# Versie_3.net
KiCad netlist of a schematic drawn in EAGLE
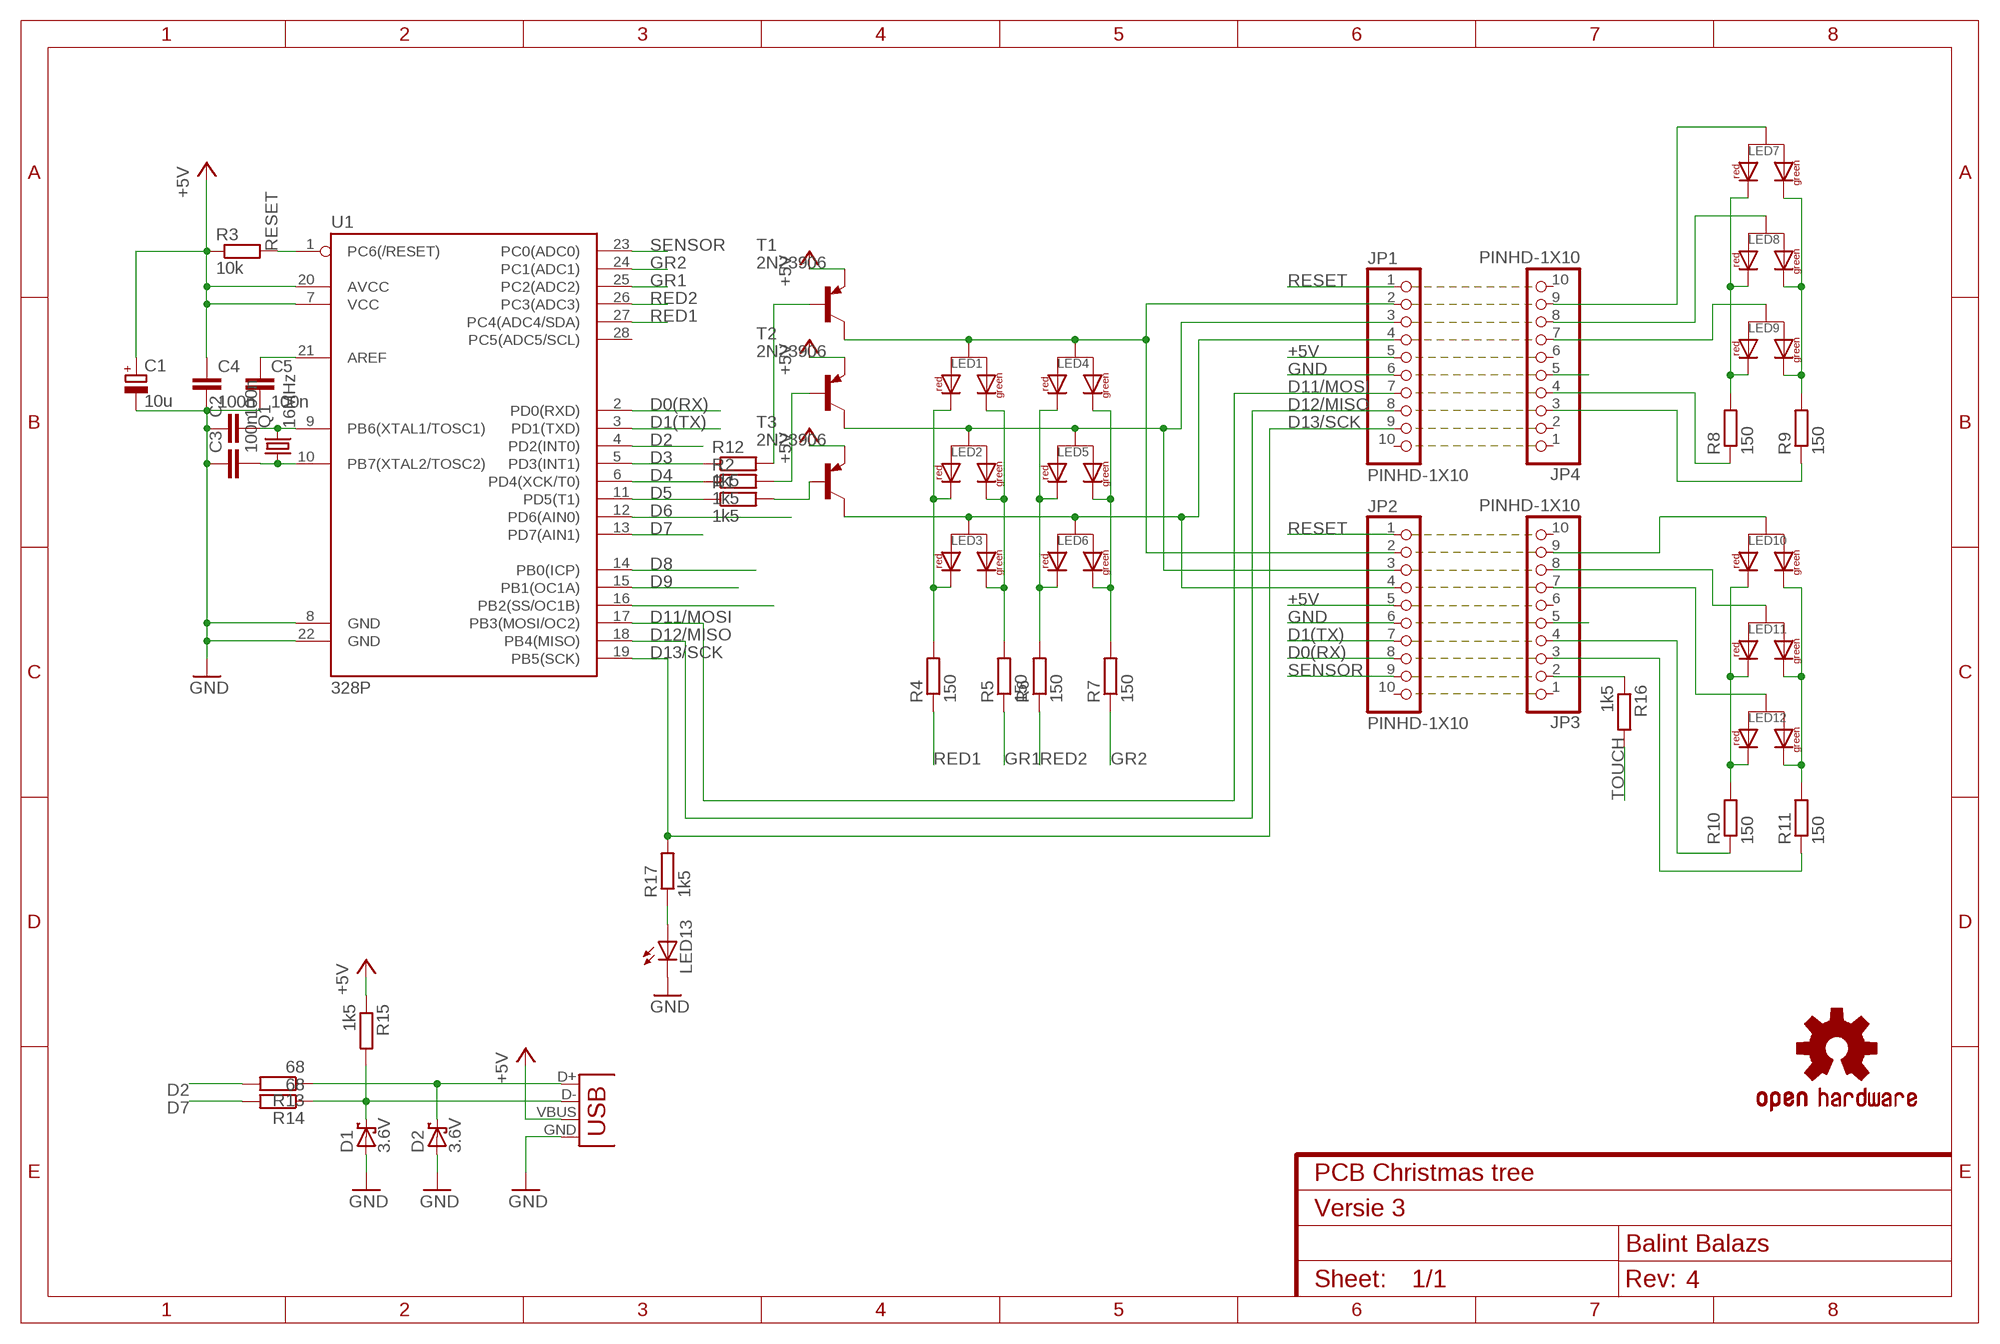
[diagram p0: schematic, sheet 1]

(export (version "E")
  (design (tool "Eeschema 10.0.6"))
  (components
    (comp (ref "C1")
      (value "10u")
      (footprint "eagle-import:E2-4")
      (libsource (lib "eagle-import") (part "CPOL-EUE2-4"))
    )
    (comp (ref "C2")
      (value "100n")
      (footprint "eagle-import:C025-024X044")
      (libsource (lib "eagle-import") (part "C-EU025-024X044"))
    )
    (comp (ref "C3")
      (value "100n")
      (footprint "eagle-import:C025-024X044")
      (libsource (lib "eagle-import") (part "C-EU025-024X044"))
    )
    (comp (ref "C4")
      (value "100n")
      (footprint "eagle-import:C025-024X044")
      (libsource (lib "eagle-import") (part "C-EU025-024X044"))
    )
    (comp (ref "C5")
      (value "100n")
      (footprint "eagle-import:C025-024X044")
      (libsource (lib "eagle-import") (part "C-EU025-024X044"))
    )
    (comp (ref "D1")
      (value "3.6V")
      (footprint "eagle-import:DO41-7.6")
      (libsource (lib "eagle-import") (part "1N5817-B"))
    )
    (comp (ref "D2")
      (value "3.6V")
      (footprint "eagle-import:DO41-7.6")
      (libsource (lib "eagle-import") (part "1N5817-B"))
    )
    (comp (ref "JP1")
      (value "PINHD-1X10")
      (footprint "eagle-import:1X10-BIG")
      (libsource (lib "eagle-import") (part "PINHD-1X10"))
    )
    (comp (ref "JP2")
      (value "PINHD-1X10")
      (footprint "eagle-import:1X10-BIG")
      (libsource (lib "eagle-import") (part "PINHD-1X10"))
    )
    (comp (ref "JP3")
      (value "PINHD-1X10")
      (footprint "eagle-import:1X10-BIG")
      (libsource (lib "eagle-import") (part "PINHD-1X10"))
    )
    (comp (ref "JP4")
      (value "PINHD-1X10")
      (footprint "eagle-import:1X10-BIG")
      (libsource (lib "eagle-import") (part "PINHD-1X10"))
    )
    (comp (ref "LED1")
      (value "KPBA-3010SURKCGKC3MM")
      (footprint "eagle-import:3MMLED")
      (libsource (lib "eagle-import") (part "KPBA-3010SURKCGKC3MM"))
    )
    (comp (ref "LED2")
      (value "KPBA-3010SURKCGKC3MM")
      (footprint "eagle-import:3MMLED")
      (libsource (lib "eagle-import") (part "KPBA-3010SURKCGKC3MM"))
    )
    (comp (ref "LED3")
      (value "KPBA-3010SURKCGKC3MM")
      (footprint "eagle-import:3MMLED")
      (libsource (lib "eagle-import") (part "KPBA-3010SURKCGKC3MM"))
    )
    (comp (ref "LED4")
      (value "KPBA-3010SURKCGKC3MM")
      (footprint "eagle-import:3MMLED")
      (libsource (lib "eagle-import") (part "KPBA-3010SURKCGKC3MM"))
    )
    (comp (ref "LED5")
      (value "KPBA-3010SURKCGKC3MM")
      (footprint "eagle-import:3MMLED")
      (libsource (lib "eagle-import") (part "KPBA-3010SURKCGKC3MM"))
    )
    (comp (ref "LED6")
      (value "KPBA-3010SURKCGKC3MM")
      (footprint "eagle-import:3MMLED")
      (libsource (lib "eagle-import") (part "KPBA-3010SURKCGKC3MM"))
    )
    (comp (ref "LED7")
      (value "KPBA-3010SURKCGKC3MM")
      (footprint "eagle-import:3MMLED")
      (libsource (lib "eagle-import") (part "KPBA-3010SURKCGKC3MM"))
    )
    (comp (ref "LED8")
      (value "KPBA-3010SURKCGKC3MM")
      (footprint "eagle-import:3MMLED")
      (libsource (lib "eagle-import") (part "KPBA-3010SURKCGKC3MM"))
    )
    (comp (ref "LED9")
      (value "KPBA-3010SURKCGKC3MM")
      (footprint "eagle-import:3MMLED")
      (libsource (lib "eagle-import") (part "KPBA-3010SURKCGKC3MM"))
    )
    (comp (ref "LED10")
      (value "KPBA-3010SURKCGKC3MM")
      (footprint "eagle-import:3MMLED")
      (libsource (lib "eagle-import") (part "KPBA-3010SURKCGKC3MM"))
    )
    (comp (ref "LED11")
      (value "KPBA-3010SURKCGKC3MM")
      (footprint "eagle-import:3MMLED")
      (libsource (lib "eagle-import") (part "KPBA-3010SURKCGKC3MM"))
    )
    (comp (ref "LED12")
      (value "KPBA-3010SURKCGKC3MM")
      (footprint "eagle-import:3MMLED")
      (libsource (lib "eagle-import") (part "KPBA-3010SURKCGKC3MM"))
    )
    (comp (ref "LED13")
      (value "LED5MM")
      (footprint "eagle-import:LED5MM")
      (libsource (lib "eagle-import") (part "LED5MM"))
    )
    (comp (ref "LOGO1")
      (value "OSHW-LOGOM")
      (footprint "eagle-import:OSHW-LOGO-M")
      (libsource (lib "eagle-import") (part "OSHW-LOGOM"))
    )
    (comp (ref "Q1")
      (value "16MHz")
      (footprint "eagle-import:HC49_S")
      (libsource (lib "eagle-import") (part "CRYSTALHC49S"))
    )
    (comp (ref "R1")
      (value "1k5")
      (footprint "eagle-import:0204_7")
      (libsource (lib "eagle-import") (part "R-EU_0204/7"))
    )
    (comp (ref "R2")
      (value "1k5")
      (footprint "eagle-import:0204_7")
      (libsource (lib "eagle-import") (part "R-EU_0204/7"))
    )
    (comp (ref "R3")
      (value "10k")
      (footprint "eagle-import:0204_7")
      (libsource (lib "eagle-import") (part "resistor_R-EU_0204/7"))
    )
    (comp (ref "R4")
      (value "150")
      (footprint "eagle-import:0204_7")
      (libsource (lib "eagle-import") (part "resistor_R-EU_0204/7"))
    )
    (comp (ref "R5")
      (value "150")
      (footprint "eagle-import:0204_7")
      (libsource (lib "eagle-import") (part "resistor_R-EU_0204/7"))
    )
    (comp (ref "R6")
      (value "150")
      (footprint "eagle-import:0204_7")
      (libsource (lib "eagle-import") (part "resistor_R-EU_0204/7"))
    )
    (comp (ref "R7")
      (value "150")
      (footprint "eagle-import:0204_7")
      (libsource (lib "eagle-import") (part "resistor_R-EU_0204/7"))
    )
    (comp (ref "R8")
      (value "150")
      (footprint "eagle-import:0204_7")
      (libsource (lib "eagle-import") (part "resistor_R-EU_0204/7"))
    )
    (comp (ref "R9")
      (value "150")
      (footprint "eagle-import:0204_7")
      (libsource (lib "eagle-import") (part "resistor_R-EU_0204/7"))
    )
    (comp (ref "R10")
      (value "150")
      (footprint "eagle-import:0204_7")
      (libsource (lib "eagle-import") (part "resistor_R-EU_0204/7"))
    )
    (comp (ref "R11")
      (value "150")
      (footprint "eagle-import:0204_7")
      (libsource (lib "eagle-import") (part "resistor_R-EU_0204/7"))
    )
    (comp (ref "R12")
      (value "1k5")
      (footprint "eagle-import:0204_7")
      (libsource (lib "eagle-import") (part "R-EU_0204/7"))
    )
    (comp (ref "R13")
      (value "68")
      (footprint "eagle-import:0204_7")
      (libsource (lib "eagle-import") (part "resistor_R-EU_0204/7"))
    )
    (comp (ref "R14")
      (value "68")
      (footprint "eagle-import:0204_7")
      (libsource (lib "eagle-import") (part "resistor_R-EU_0204/7"))
    )
    (comp (ref "R15")
      (value "1k5")
      (footprint "eagle-import:0204_7")
      (libsource (lib "eagle-import") (part "resistor_R-EU_0204/7"))
    )
    (comp (ref "R16")
      (value "1k5")
      (footprint "eagle-import:0204_7")
      (libsource (lib "eagle-import") (part "resistor_R-EU_0204/7"))
    )
    (comp (ref "R17")
      (value "1k5")
      (footprint "eagle-import:0204_7")
      (libsource (lib "eagle-import") (part "resistor_R-EU_0204/7"))
    )
    (comp (ref "T1")
      (value "2N23906")
      (footprint "eagle-import:TO92-STRAIGHT")
      (libsource (lib "eagle-import") (part "PNP"))
    )
    (comp (ref "T2")
      (value "2N23906")
      (footprint "eagle-import:TO92-STRAIGHT")
      (libsource (lib "eagle-import") (part "PNP"))
    )
    (comp (ref "T3")
      (value "2N23906")
      (footprint "eagle-import:TO92-STRAIGHT")
      (libsource (lib "eagle-import") (part "PNP"))
    )
    (comp (ref "U1")
      (value "328P")
      (footprint "eagle-import:DIP28")
      (libsource (lib "eagle-import") (part "ATMEGA328P_PDIP"))
    )
    (comp (ref "X1")
      (value "USBMINITHT")
      (footprint "eagle-import:USB-MINIB-THT")
      (libsource (lib "eagle-import") (part "USBMINITHT"))
    )
  )
  (nets
    (net (code "1") (name "+5V") (class "Default")
      (node (ref "C1") (pin "+") (pinfunction "+_+") (pintype "passive"))
      (node (ref "C4") (pin "1") (pinfunction "1_1") (pintype "passive"))
      (node (ref "JP1") (pin "5") (pinfunction "5_5") (pintype "passive"))
      (node (ref "JP2") (pin "5") (pinfunction "5_5") (pintype "passive"))
      (node (ref "R15") (pin "1") (pinfunction "1_1") (pintype "passive"))
      (node (ref "R3") (pin "1") (pinfunction "1_1") (pintype "passive"))
      (node (ref "T1") (pin "E") (pinfunction "E_E") (pintype "passive"))
      (node (ref "T2") (pin "E") (pinfunction "E_E") (pintype "passive"))
      (node (ref "T3") (pin "E") (pinfunction "E_E") (pintype "passive"))
      (node (ref "U1") (pin "20") (pinfunction "AVCC_20") (pintype "bidirectional"))
      (node (ref "U1") (pin "7") (pinfunction "VCC_7") (pintype "bidirectional"))
      (node (ref "X1") (pin "VBUS") (pinfunction "VBUS_VBUS") (pintype "bidirectional"))
    )
    (net (code "2") (name "/D0(RX)") (class "Default")
      (node (ref "JP2") (pin "8") (pinfunction "8_8") (pintype "passive"))
      (node (ref "U1") (pin "2") (pinfunction "PD0(RXD)_2") (pintype "bidirectional"))
    )
    (net (code "3") (name "/D1(TX)") (class "Default")
      (node (ref "JP2") (pin "7") (pinfunction "7_7") (pintype "passive"))
      (node (ref "U1") (pin "3") (pinfunction "PD1(TXD)_3") (pintype "bidirectional"))
    )
    (net (code "4") (name "/D2") (class "Default")
      (node (ref "R13") (pin "2") (pinfunction "2_2") (pintype "passive"))
      (node (ref "U1") (pin "4") (pinfunction "PD2(INT0)_4") (pintype "bidirectional"))
    )
    (net (code "5") (name "/D3") (class "Default")
      (node (ref "R12") (pin "1") (pinfunction "1_1") (pintype "passive"))
      (node (ref "U1") (pin "5") (pinfunction "PD3(INT1)_5") (pintype "bidirectional"))
    )
    (net (code "6") (name "/D4") (class "Default")
      (node (ref "R2") (pin "1") (pinfunction "1_1") (pintype "passive"))
      (node (ref "U1") (pin "6") (pinfunction "PD4(XCK/T0)_6") (pintype "bidirectional"))
    )
    (net (code "7") (name "/D5") (class "Default")
      (node (ref "R1") (pin "1") (pinfunction "1_1") (pintype "passive"))
      (node (ref "U1") (pin "11") (pinfunction "PD5(T1)_11") (pintype "bidirectional"))
    )
    (net (code "8") (name "/D6") (class "Default")
      (node (ref "U1") (pin "12") (pinfunction "PD6(AIN0)_12") (pintype "bidirectional"))
    )
    (net (code "9") (name "/D7") (class "Default")
      (node (ref "R14") (pin "2") (pinfunction "2_2") (pintype "passive"))
      (node (ref "U1") (pin "13") (pinfunction "PD7(AIN1)_13") (pintype "bidirectional"))
    )
    (net (code "10") (name "/D8") (class "Default")
      (node (ref "U1") (pin "14") (pinfunction "PB0(ICP)_14") (pintype "bidirectional"))
    )
    (net (code "11") (name "/D9") (class "Default")
      (node (ref "U1") (pin "15") (pinfunction "PB1(OC1A)_15") (pintype "bidirectional"))
    )
    (net (code "12") (name "/D11{slash}MOSI") (class "Default")
      (node (ref "JP1") (pin "7") (pinfunction "7_7") (pintype "passive"))
      (node (ref "U1") (pin "17") (pinfunction "PB3(MOSI/OC2)_17") (pintype "bidirectional"))
    )
    (net (code "13") (name "/D12{slash}MISO") (class "Default")
      (node (ref "JP1") (pin "8") (pinfunction "8_8") (pintype "passive"))
      (node (ref "U1") (pin "18") (pinfunction "PB4(MISO)_18") (pintype "bidirectional"))
    )
    (net (code "14") (name "/D13{slash}SCK") (class "Default")
      (node (ref "JP1") (pin "9") (pinfunction "9_9") (pintype "passive"))
      (node (ref "R17") (pin "2") (pinfunction "2_2") (pintype "passive"))
      (node (ref "U1") (pin "19") (pinfunction "PB5(SCK)_19") (pintype "bidirectional"))
    )
    (net (code "15") (name "/GR1") (class "Default")
      (node (ref "R5") (pin "1") (pinfunction "1_1") (pintype "passive"))
      (node (ref "U1") (pin "25") (pinfunction "PC2(ADC2)_25") (pintype "bidirectional"))
    )
    (net (code "16") (name "/GR2") (class "Default")
      (node (ref "R7") (pin "1") (pinfunction "1_1") (pintype "passive"))
      (node (ref "U1") (pin "24") (pinfunction "PC1(ADC1)_24") (pintype "bidirectional"))
    )
    (net (code "17") (name "/RED1") (class "Default")
      (node (ref "R4") (pin "1") (pinfunction "1_1") (pintype "passive"))
      (node (ref "U1") (pin "27") (pinfunction "PC4(ADC4/SDA)_27") (pintype "bidirectional"))
    )
    (net (code "18") (name "/RED2") (class "Default")
      (node (ref "R6") (pin "1") (pinfunction "1_1") (pintype "passive"))
      (node (ref "U1") (pin "26") (pinfunction "PC3(ADC3)_26") (pintype "bidirectional"))
    )
    (net (code "19") (name "/RESET") (class "Default")
      (node (ref "JP1") (pin "1") (pinfunction "1_1") (pintype "passive"))
      (node (ref "JP2") (pin "1") (pinfunction "1_1") (pintype "passive"))
      (node (ref "R3") (pin "2") (pinfunction "2_2") (pintype "passive"))
      (node (ref "U1") (pin "1") (pinfunction "PC6(/RESET)_1") (pintype "bidirectional"))
    )
    (net (code "20") (name "/SENSOR") (class "Default")
      (node (ref "JP2") (pin "9") (pinfunction "9_9") (pintype "passive"))
      (node (ref "U1") (pin "23") (pinfunction "PC0(ADC0)_23") (pintype "bidirectional"))
    )
    (net (code "21") (name "/TOUCH") (class "Default")
      (node (ref "R16") (pin "2") (pinfunction "2_2") (pintype "passive"))
    )
    (net (code "22") (name "GND") (class "Default")
      (node (ref "C1") (pin "-") (pinfunction "-_-") (pintype "passive"))
      (node (ref "C2") (pin "1") (pinfunction "1_1") (pintype "passive"))
      (node (ref "C3") (pin "1") (pinfunction "1_1") (pintype "passive"))
      (node (ref "C4") (pin "2") (pinfunction "2_2") (pintype "passive"))
      (node (ref "C5") (pin "2") (pinfunction "2_2") (pintype "passive"))
      (node (ref "D1") (pin "A") (pinfunction "A_A") (pintype "passive"))
      (node (ref "D2") (pin "A") (pinfunction "A_A") (pintype "passive"))
      (node (ref "JP1") (pin "6") (pinfunction "6_6") (pintype "passive"))
      (node (ref "JP2") (pin "6") (pinfunction "6_6") (pintype "passive"))
      (node (ref "LED13") (pin "K") (pinfunction "C_K") (pintype "passive"))
      (node (ref "U1") (pin "22") (pinfunction "GND_22") (pintype "bidirectional"))
      (node (ref "U1") (pin "8") (pinfunction "GND_8") (pintype "bidirectional"))
      (node (ref "X1") (pin "GND") (pinfunction "GND_GND") (pintype "bidirectional"))
    )
    (net (code "23") (name "Net-(D1-PadC)") (class "Default")
      (node (ref "D1") (pin "C") (pinfunction "C_C") (pintype "passive"))
      (node (ref "R14") (pin "1") (pinfunction "1_1") (pintype "passive"))
      (node (ref "R15") (pin "2") (pinfunction "2_2") (pintype "passive"))
      (node (ref "X1") (pin "D-") (pinfunction "D-_D-") (pintype "bidirectional"))
    )
    (net (code "24") (name "Net-(D2-PadC)") (class "Default")
      (node (ref "D2") (pin "C") (pinfunction "C_C") (pintype "passive"))
      (node (ref "R13") (pin "1") (pinfunction "1_1") (pintype "passive"))
      (node (ref "X1") (pin "D+") (pinfunction "D+_D+") (pintype "bidirectional"))
    )
    (net (code "25") (name "Net-(JP3-Pad2)") (class "Default")
      (node (ref "JP3") (pin "2") (pinfunction "2_2") (pintype "passive"))
      (node (ref "R16") (pin "1") (pinfunction "1_1") (pintype "passive"))
    )
    (net (code "26") (name "Net-(JP3-Pad3)") (class "Default")
      (node (ref "JP3") (pin "3") (pinfunction "3_3") (pintype "passive"))
      (node (ref "R11") (pin "1") (pinfunction "1_1") (pintype "passive"))
    )
    (net (code "27") (name "Net-(JP3-Pad4)") (class "Default")
      (node (ref "JP3") (pin "4") (pinfunction "4_4") (pintype "passive"))
      (node (ref "R10") (pin "1") (pinfunction "1_1") (pintype "passive"))
    )
    (net (code "28") (name "Net-(JP4-Pad3)") (class "Default")
      (node (ref "JP4") (pin "3") (pinfunction "3_3") (pintype "passive"))
      (node (ref "R9") (pin "1") (pinfunction "1_1") (pintype "passive"))
    )
    (net (code "29") (name "Net-(JP4-Pad4)") (class "Default")
      (node (ref "JP4") (pin "4") (pinfunction "4_4") (pintype "passive"))
      (node (ref "R8") (pin "1") (pinfunction "1_1") (pintype "passive"))
    )
    (net (code "30") (name "Net-(LED1-P$1)") (class "Default")
      (node (ref "JP1") (pin "2") (pinfunction "2_2") (pintype "passive"))
      (node (ref "JP2") (pin "2") (pinfunction "2_2") (pintype "passive"))
      (node (ref "LED1") (pin "+") (pinfunction "P$1_+") (pintype "passive"))
      (node (ref "LED4") (pin "+") (pinfunction "P$1_+") (pintype "passive"))
      (node (ref "T1") (pin "C") (pinfunction "C_C") (pintype "passive"))
    )
    (net (code "31") (name "Net-(LED1-P$2)") (class "Default")
      (node (ref "LED1") (pin "-1") (pinfunction "P$2_-1") (pintype "passive"))
      (node (ref "LED2") (pin "-1") (pinfunction "P$2_-1") (pintype "passive"))
      (node (ref "LED3") (pin "-1") (pinfunction "P$2_-1") (pintype "passive"))
      (node (ref "R4") (pin "2") (pinfunction "2_2") (pintype "passive"))
    )
    (net (code "32") (name "Net-(LED1-P$3)") (class "Default")
      (node (ref "LED1") (pin "-2") (pinfunction "P$3_-2") (pintype "passive"))
      (node (ref "LED2") (pin "-2") (pinfunction "P$3_-2") (pintype "passive"))
      (node (ref "LED3") (pin "-2") (pinfunction "P$3_-2") (pintype "passive"))
      (node (ref "R5") (pin "2") (pinfunction "2_2") (pintype "passive"))
    )
    (net (code "33") (name "Net-(LED2-P$1)") (class "Default")
      (node (ref "JP1") (pin "3") (pinfunction "3_3") (pintype "passive"))
      (node (ref "JP2") (pin "3") (pinfunction "3_3") (pintype "passive"))
      (node (ref "LED2") (pin "+") (pinfunction "P$1_+") (pintype "passive"))
      (node (ref "LED5") (pin "+") (pinfunction "P$1_+") (pintype "passive"))
      (node (ref "T2") (pin "C") (pinfunction "C_C") (pintype "passive"))
    )
    (net (code "34") (name "Net-(LED3-P$1)") (class "Default")
      (node (ref "JP1") (pin "4") (pinfunction "4_4") (pintype "passive"))
      (node (ref "JP2") (pin "4") (pinfunction "4_4") (pintype "passive"))
      (node (ref "LED3") (pin "+") (pinfunction "P$1_+") (pintype "passive"))
      (node (ref "LED6") (pin "+") (pinfunction "P$1_+") (pintype "passive"))
      (node (ref "T3") (pin "C") (pinfunction "C_C") (pintype "passive"))
    )
    (net (code "35") (name "Net-(LED4-P$2)") (class "Default")
      (node (ref "LED4") (pin "-1") (pinfunction "P$2_-1") (pintype "passive"))
      (node (ref "LED5") (pin "-1") (pinfunction "P$2_-1") (pintype "passive"))
      (node (ref "LED6") (pin "-1") (pinfunction "P$2_-1") (pintype "passive"))
      (node (ref "R6") (pin "2") (pinfunction "2_2") (pintype "passive"))
    )
    (net (code "36") (name "Net-(LED4-P$3)") (class "Default")
      (node (ref "LED4") (pin "-2") (pinfunction "P$3_-2") (pintype "passive"))
      (node (ref "LED5") (pin "-2") (pinfunction "P$3_-2") (pintype "passive"))
      (node (ref "LED6") (pin "-2") (pinfunction "P$3_-2") (pintype "passive"))
      (node (ref "R7") (pin "2") (pinfunction "2_2") (pintype "passive"))
    )
    (net (code "37") (name "Net-(LED7-P$1)") (class "Default")
      (node (ref "JP4") (pin "9") (pinfunction "9_9") (pintype "passive"))
      (node (ref "LED7") (pin "+") (pinfunction "P$1_+") (pintype "passive"))
    )
    (net (code "38") (name "Net-(LED7-P$2)") (class "Default")
      (node (ref "LED7") (pin "-1") (pinfunction "P$2_-1") (pintype "passive"))
      (node (ref "LED8") (pin "-1") (pinfunction "P$2_-1") (pintype "passive"))
      (node (ref "LED9") (pin "-1") (pinfunction "P$2_-1") (pintype "passive"))
      (node (ref "R8") (pin "2") (pinfunction "2_2") (pintype "passive"))
    )
    (net (code "39") (name "Net-(LED7-P$3)") (class "Default")
      (node (ref "LED7") (pin "-2") (pinfunction "P$3_-2") (pintype "passive"))
      (node (ref "LED8") (pin "-2") (pinfunction "P$3_-2") (pintype "passive"))
      (node (ref "LED9") (pin "-2") (pinfunction "P$3_-2") (pintype "passive"))
      (node (ref "R9") (pin "2") (pinfunction "2_2") (pintype "passive"))
    )
    (net (code "40") (name "Net-(LED8-P$1)") (class "Default")
      (node (ref "JP4") (pin "8") (pinfunction "8_8") (pintype "passive"))
      (node (ref "LED8") (pin "+") (pinfunction "P$1_+") (pintype "passive"))
    )
    (net (code "41") (name "Net-(LED9-P$1)") (class "Default")
      (node (ref "JP4") (pin "7") (pinfunction "7_7") (pintype "passive"))
      (node (ref "LED9") (pin "+") (pinfunction "P$1_+") (pintype "passive"))
    )
    (net (code "42") (name "Net-(LED10-P$1)") (class "Default")
      (node (ref "JP3") (pin "9") (pinfunction "9_9") (pintype "passive"))
      (node (ref "LED10") (pin "+") (pinfunction "P$1_+") (pintype "passive"))
    )
    (net (code "43") (name "Net-(LED10-P$2)") (class "Default")
      (node (ref "LED10") (pin "-1") (pinfunction "P$2_-1") (pintype "passive"))
      (node (ref "LED11") (pin "-1") (pinfunction "P$2_-1") (pintype "passive"))
      (node (ref "LED12") (pin "-1") (pinfunction "P$2_-1") (pintype "passive"))
      (node (ref "R10") (pin "2") (pinfunction "2_2") (pintype "passive"))
    )
    (net (code "44") (name "Net-(LED10-P$3)") (class "Default")
      (node (ref "LED10") (pin "-2") (pinfunction "P$3_-2") (pintype "passive"))
      (node (ref "LED11") (pin "-2") (pinfunction "P$3_-2") (pintype "passive"))
      (node (ref "LED12") (pin "-2") (pinfunction "P$3_-2") (pintype "passive"))
      (node (ref "R11") (pin "2") (pinfunction "2_2") (pintype "passive"))
    )
    (net (code "45") (name "Net-(LED11-P$1)") (class "Default")
      (node (ref "JP3") (pin "8") (pinfunction "8_8") (pintype "passive"))
      (node (ref "LED11") (pin "+") (pinfunction "P$1_+") (pintype "passive"))
    )
    (net (code "46") (name "Net-(LED12-P$1)") (class "Default")
      (node (ref "JP3") (pin "7") (pinfunction "7_7") (pintype "passive"))
      (node (ref "LED12") (pin "+") (pinfunction "P$1_+") (pintype "passive"))
    )
    (net (code "47") (name "Net-(LED13-PadA)") (class "Default")
      (node (ref "LED13") (pin "A") (pinfunction "A_A") (pintype "passive"))
      (node (ref "R17") (pin "1") (pinfunction "1_1") (pintype "passive"))
    )
    (net (code "48") (name "Net-(R1-Pad2)") (class "Default")
      (node (ref "R1") (pin "2") (pinfunction "2_2") (pintype "passive"))
      (node (ref "T3") (pin "B") (pinfunction "B_B") (pintype "passive"))
    )
    (net (code "49") (name "Net-(R2-Pad2)") (class "Default")
      (node (ref "R2") (pin "2") (pinfunction "2_2") (pintype "passive"))
      (node (ref "T2") (pin "B") (pinfunction "B_B") (pintype "passive"))
    )
    (net (code "50") (name "Net-(R12-Pad2)") (class "Default")
      (node (ref "R12") (pin "2") (pinfunction "2_2") (pintype "passive"))
      (node (ref "T1") (pin "B") (pinfunction "B_B") (pintype "passive"))
    )
    (net (code "51") (name "Net-(U1-AREF)") (class "Default")
      (node (ref "C5") (pin "1") (pinfunction "1_1") (pintype "passive"))
      (node (ref "U1") (pin "21") (pinfunction "AREF_21") (pintype "bidirectional"))
    )
    (net (code "52") (name "Net-(U1-PB6(XTAL1{slash}TOSC1))") (class "Default")
      (node (ref "C2") (pin "2") (pinfunction "2_2") (pintype "passive"))
      (node (ref "Q1") (pin "2") (pinfunction "2_2") (pintype "passive"))
      (node (ref "U1") (pin "9") (pinfunction "PB6(XTAL1/TOSC1)_9") (pintype "bidirectional"))
    )
    (net (code "53") (name "Net-(U1-PB7(XTAL2{slash}TOSC2))") (class "Default")
      (node (ref "C3") (pin "2") (pinfunction "2_2") (pintype "passive"))
      (node (ref "Q1") (pin "1") (pinfunction "1_1") (pintype "passive"))
      (node (ref "U1") (pin "10") (pinfunction "PB7(XTAL2/TOSC2)_10") (pintype "bidirectional"))
    )
    (net (code "54") (name "unconnected-(JP1-Pad10)") (class "Default")
      (node (ref "JP1") (pin "10") (pinfunction "10_10") (pintype "passive"))
    )
    (net (code "55") (name "unconnected-(JP2-Pad10)") (class "Default")
      (node (ref "JP2") (pin "10") (pinfunction "10_10") (pintype "passive"))
    )
    (net (code "56") (name "unconnected-(JP3-Pad1)") (class "Default")
      (node (ref "JP3") (pin "1") (pinfunction "1_1") (pintype "passive"))
    )
    (net (code "57") (name "unconnected-(JP3-Pad5)") (class "Default")
      (node (ref "JP3") (pin "5") (pinfunction "5_5") (pintype "passive"))
    )
    (net (code "58") (name "unconnected-(JP3-Pad6)") (class "Default")
      (node (ref "JP3") (pin "6") (pinfunction "6_6") (pintype "passive"))
    )
    (net (code "59") (name "unconnected-(JP3-Pad10)") (class "Default")
      (node (ref "JP3") (pin "10") (pinfunction "10_10") (pintype "passive"))
    )
    (net (code "60") (name "unconnected-(JP4-Pad1)") (class "Default")
      (node (ref "JP4") (pin "1") (pinfunction "1_1") (pintype "passive"))
    )
    (net (code "61") (name "unconnected-(JP4-Pad2)") (class "Default")
      (node (ref "JP4") (pin "2") (pinfunction "2_2") (pintype "passive"))
    )
    (net (code "62") (name "unconnected-(JP4-Pad5)") (class "Default")
      (node (ref "JP4") (pin "5") (pinfunction "5_5") (pintype "passive"))
    )
    (net (code "63") (name "unconnected-(JP4-Pad6)") (class "Default")
      (node (ref "JP4") (pin "6") (pinfunction "6_6") (pintype "passive"))
    )
    (net (code "64") (name "unconnected-(JP4-Pad10)") (class "Default")
      (node (ref "JP4") (pin "10") (pinfunction "10_10") (pintype "passive"))
    )
    (net (code "65") (name "unconnected-(U1-PB2(SS{slash}OC1B)-Pad16)") (class "Default")
      (node (ref "U1") (pin "16") (pinfunction "PB2(SS/OC1B)_16") (pintype "bidirectional"))
    )
    (net (code "66") (name "unconnected-(U1-PC5(ADC5{slash}SCL)-Pad28)") (class "Default")
      (node (ref "U1") (pin "28") (pinfunction "PC5(ADC5/SCL)_28") (pintype "bidirectional"))
    )
  )
)
